# Z7_POWER1.net
KiCad netlist of a schematic drawn in Altium Designer
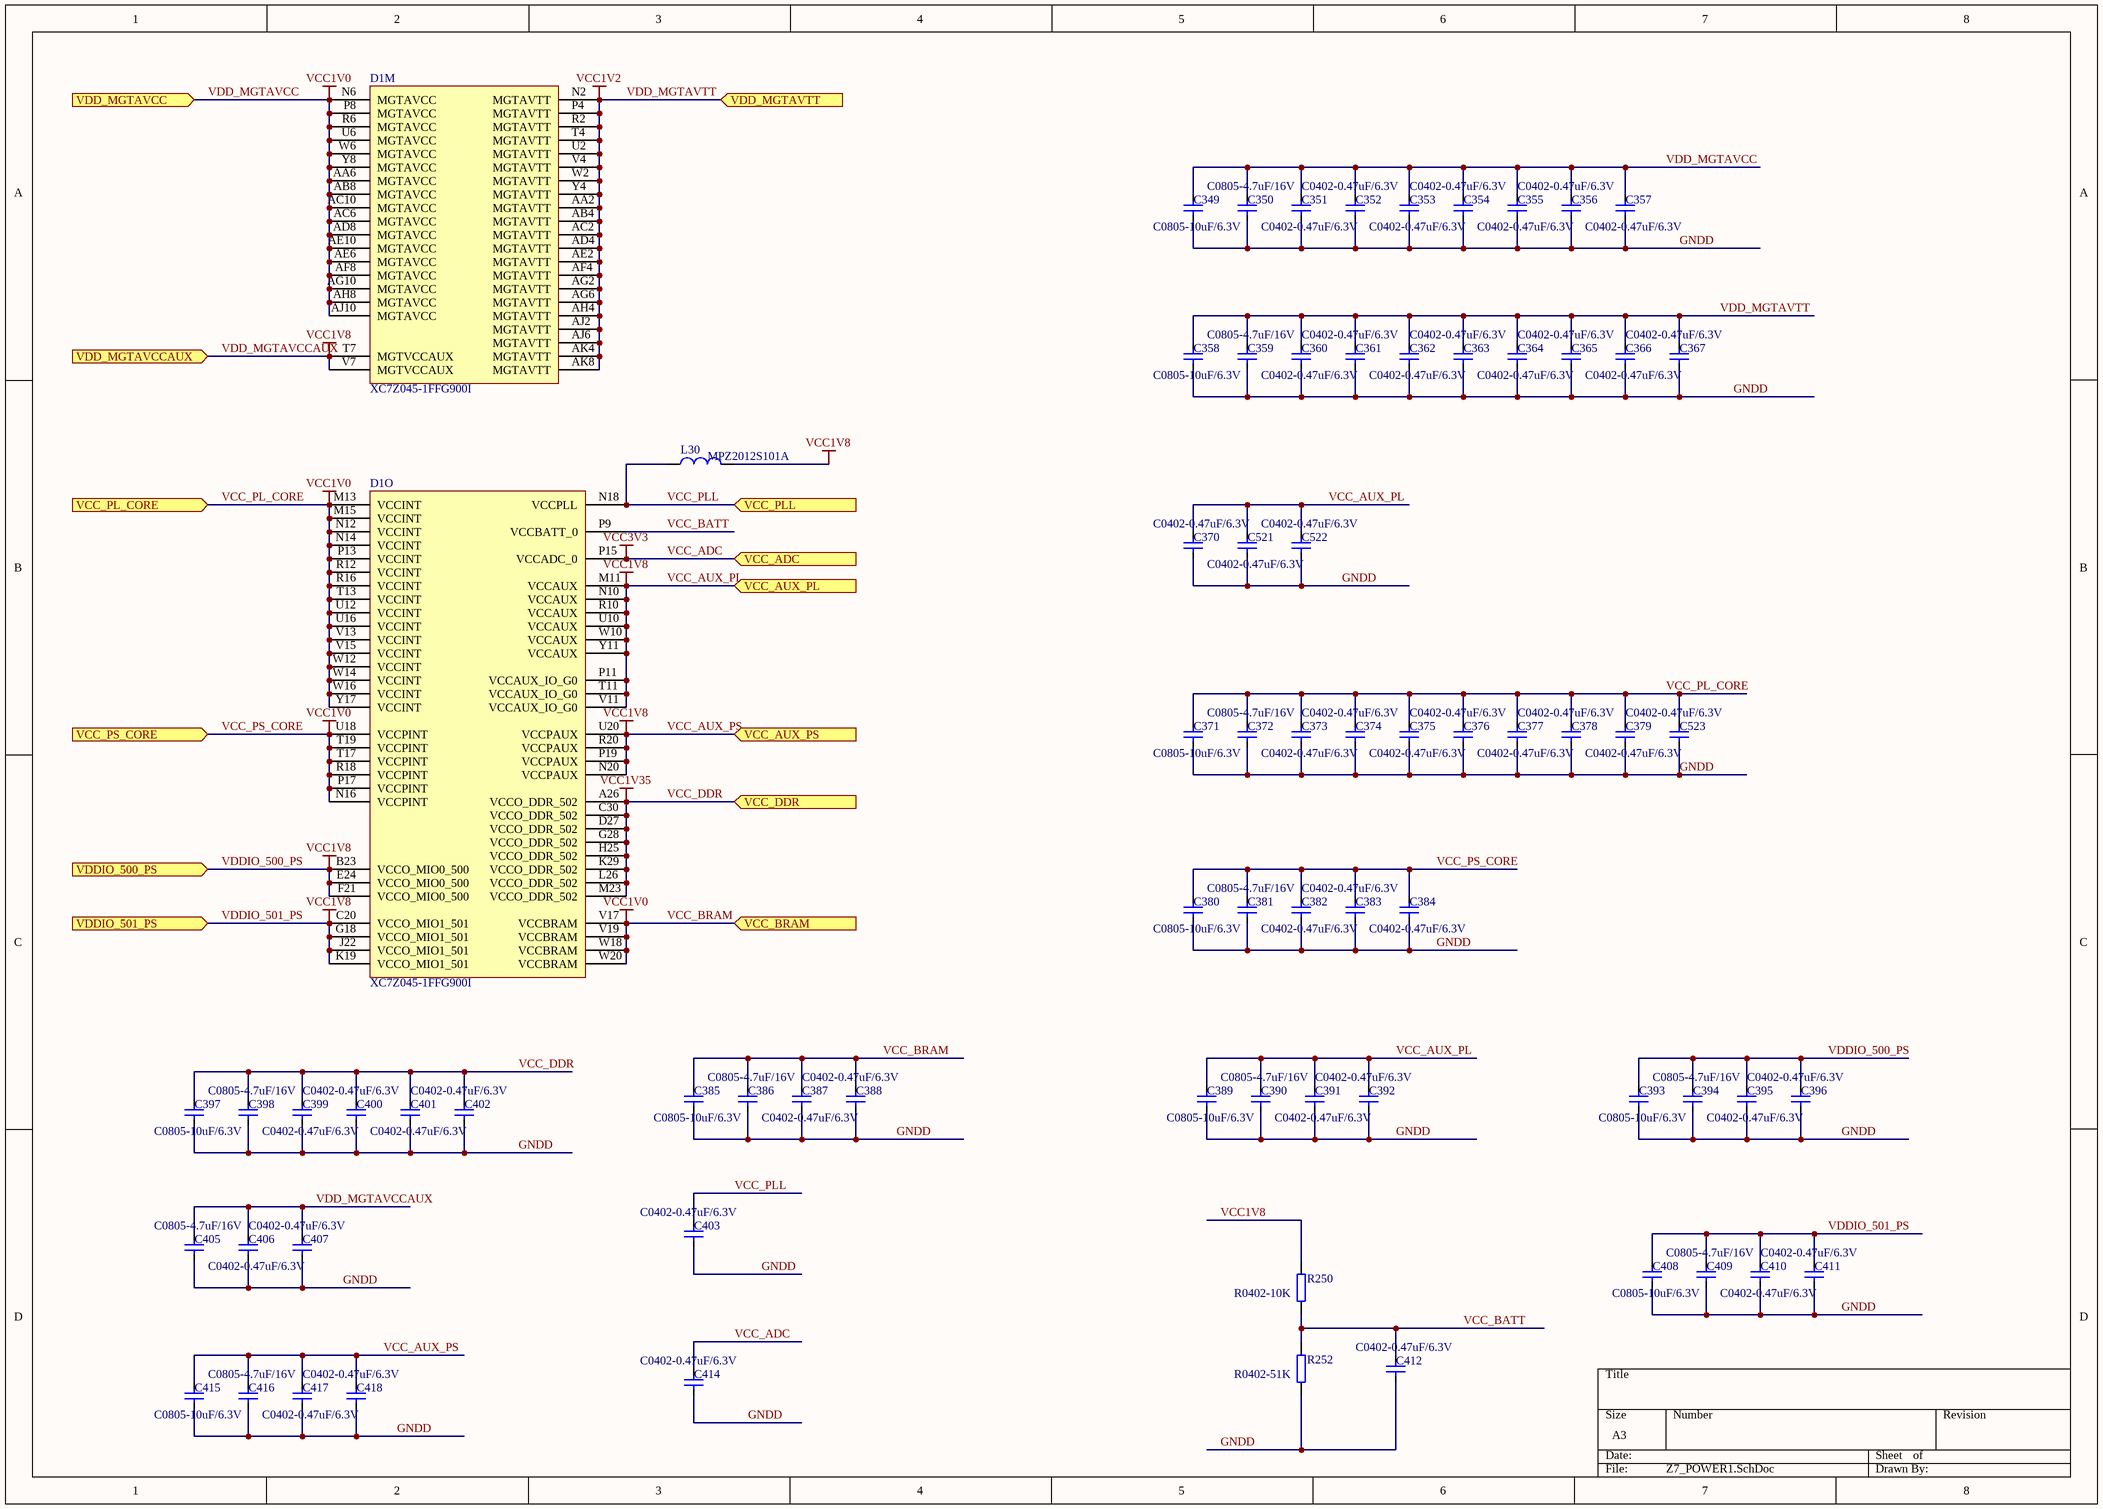
[diagram p0: Z7_POWER1.SchDoc]

(export (version "E")
  (design (tool "Eeschema 10.0.6"))
  (components
    (comp (ref "C349")
      (value "C0805-10uF/6.3V")
      (footprint "C0805")
      (fields (field (name "SCHEMATIC_PART") "CAP"))
      (libsource (lib "Database_Libs1") (part "CAP"))
    )
    (comp (ref "C350")
      (value "C0805-4.7uF/16V")
      (footprint "C0805")
      (description "X7R")
      (fields (field (name "SCHEMATIC_PART") "CAP") (field (name "MANUFACTURER") "SAMSUNG"))
      (libsource (lib "Database_Libs1") (part "CAP"))
    )
    (comp (ref "C351")
      (value "C0402-0.47uF/6.3V")
      (footprint "C0402")
      (description "X7R")
      (fields (field (name "SCHEMATIC_PART") "CAP") (field (name "MANUFACTURER") "SAMSUNG"))
      (libsource (lib "Database_Libs1") (part "CAP"))
    )
    (comp (ref "C352")
      (value "C0402-0.47uF/6.3V")
      (footprint "C0402")
      (description "X7R")
      (fields (field (name "SCHEMATIC_PART") "CAP") (field (name "MANUFACTURER") "SAMSUNG"))
      (libsource (lib "Database_Libs1") (part "CAP"))
    )
    (comp (ref "C353")
      (value "C0402-0.47uF/6.3V")
      (footprint "C0402")
      (description "X7R")
      (fields (field (name "SCHEMATIC_PART") "CAP") (field (name "MANUFACTURER") "SAMSUNG"))
      (libsource (lib "Database_Libs1") (part "CAP"))
    )
    (comp (ref "C354")
      (value "C0402-0.47uF/6.3V")
      (footprint "C0402")
      (description "X7R")
      (fields (field (name "SCHEMATIC_PART") "CAP") (field (name "MANUFACTURER") "SAMSUNG"))
      (libsource (lib "Database_Libs1") (part "CAP"))
    )
    (comp (ref "C355")
      (value "C0402-0.47uF/6.3V")
      (footprint "C0402")
      (description "X7R")
      (fields (field (name "SCHEMATIC_PART") "CAP") (field (name "MANUFACTURER") "SAMSUNG"))
      (libsource (lib "Database_Libs1") (part "CAP"))
    )
    (comp (ref "C356")
      (value "C0402-0.47uF/6.3V")
      (footprint "C0402")
      (description "X7R")
      (fields (field (name "SCHEMATIC_PART") "CAP") (field (name "MANUFACTURER") "SAMSUNG"))
      (libsource (lib "Database_Libs1") (part "CAP"))
    )
    (comp (ref "C357")
      (value "C0402-0.47uF/6.3V")
      (footprint "C0402")
      (description "X7R")
      (fields (field (name "SCHEMATIC_PART") "CAP") (field (name "MANUFACTURER") "SAMSUNG"))
      (libsource (lib "Database_Libs1") (part "CAP"))
    )
    (comp (ref "C358")
      (value "C0805-10uF/6.3V")
      (footprint "C0805")
      (fields (field (name "SCHEMATIC_PART") "CAP"))
      (libsource (lib "Database_Libs1") (part "CAP"))
    )
    (comp (ref "C359")
      (value "C0805-4.7uF/16V")
      (footprint "C0805")
      (description "X7R")
      (fields (field (name "SCHEMATIC_PART") "CAP") (field (name "MANUFACTURER") "SAMSUNG"))
      (libsource (lib "Database_Libs1") (part "CAP"))
    )
    (comp (ref "C360")
      (value "C0402-0.47uF/6.3V")
      (footprint "C0402")
      (description "X7R")
      (fields (field (name "SCHEMATIC_PART") "CAP") (field (name "MANUFACTURER") "SAMSUNG"))
      (libsource (lib "Database_Libs1") (part "CAP"))
    )
    (comp (ref "C361")
      (value "C0402-0.47uF/6.3V")
      (footprint "C0402")
      (description "X7R")
      (fields (field (name "SCHEMATIC_PART") "CAP") (field (name "MANUFACTURER") "SAMSUNG"))
      (libsource (lib "Database_Libs1") (part "CAP"))
    )
    (comp (ref "C362")
      (value "C0402-0.47uF/6.3V")
      (footprint "C0402")
      (description "X7R")
      (fields (field (name "SCHEMATIC_PART") "CAP") (field (name "MANUFACTURER") "SAMSUNG"))
      (libsource (lib "Database_Libs1") (part "CAP"))
    )
    (comp (ref "C363")
      (value "C0402-0.47uF/6.3V")
      (footprint "C0402")
      (description "X7R")
      (fields (field (name "SCHEMATIC_PART") "CAP") (field (name "MANUFACTURER") "SAMSUNG"))
      (libsource (lib "Database_Libs1") (part "CAP"))
    )
    (comp (ref "C364")
      (value "C0402-0.47uF/6.3V")
      (footprint "C0402")
      (description "X7R")
      (fields (field (name "SCHEMATIC_PART") "CAP") (field (name "MANUFACTURER") "SAMSUNG"))
      (libsource (lib "Database_Libs1") (part "CAP"))
    )
    (comp (ref "C365")
      (value "C0402-0.47uF/6.3V")
      (footprint "C0402")
      (description "X7R")
      (fields (field (name "SCHEMATIC_PART") "CAP") (field (name "MANUFACTURER") "SAMSUNG"))
      (libsource (lib "Database_Libs1") (part "CAP"))
    )
    (comp (ref "C366")
      (value "C0402-0.47uF/6.3V")
      (footprint "C0402")
      (description "X7R")
      (fields (field (name "SCHEMATIC_PART") "CAP") (field (name "MANUFACTURER") "SAMSUNG"))
      (libsource (lib "Database_Libs1") (part "CAP"))
    )
    (comp (ref "C367")
      (value "C0402-0.47uF/6.3V")
      (footprint "C0402")
      (description "X7R")
      (fields (field (name "SCHEMATIC_PART") "CAP") (field (name "MANUFACTURER") "SAMSUNG"))
      (libsource (lib "Database_Libs1") (part "CAP"))
    )
    (comp (ref "C370")
      (value "C0402-0.47uF/6.3V")
      (footprint "C0402")
      (description "X7R")
      (fields (field (name "SCHEMATIC_PART") "CAP") (field (name "MANUFACTURER") "SAMSUNG"))
      (libsource (lib "Database_Libs1") (part "CAP"))
    )
    (comp (ref "C371")
      (value "C0805-10uF/6.3V")
      (footprint "C0805")
      (fields (field (name "SCHEMATIC_PART") "CAP"))
      (libsource (lib "Database_Libs1") (part "CAP"))
    )
    (comp (ref "C372")
      (value "C0805-4.7uF/16V")
      (footprint "C0805")
      (description "X7R")
      (fields (field (name "SCHEMATIC_PART") "CAP") (field (name "MANUFACTURER") "SAMSUNG"))
      (libsource (lib "Database_Libs1") (part "CAP"))
    )
    (comp (ref "C373")
      (value "C0402-0.47uF/6.3V")
      (footprint "C0402")
      (description "X7R")
      (fields (field (name "SCHEMATIC_PART") "CAP") (field (name "MANUFACTURER") "SAMSUNG"))
      (libsource (lib "Database_Libs1") (part "CAP"))
    )
    (comp (ref "C374")
      (value "C0402-0.47uF/6.3V")
      (footprint "C0402")
      (description "X7R")
      (fields (field (name "SCHEMATIC_PART") "CAP") (field (name "MANUFACTURER") "SAMSUNG"))
      (libsource (lib "Database_Libs1") (part "CAP"))
    )
    (comp (ref "C375")
      (value "C0402-0.47uF/6.3V")
      (footprint "C0402")
      (description "X7R")
      (fields (field (name "SCHEMATIC_PART") "CAP") (field (name "MANUFACTURER") "SAMSUNG"))
      (libsource (lib "Database_Libs1") (part "CAP"))
    )
    (comp (ref "C376")
      (value "C0402-0.47uF/6.3V")
      (footprint "C0402")
      (description "X7R")
      (fields (field (name "SCHEMATIC_PART") "CAP") (field (name "MANUFACTURER") "SAMSUNG"))
      (libsource (lib "Database_Libs1") (part "CAP"))
    )
    (comp (ref "C377")
      (value "C0402-0.47uF/6.3V")
      (footprint "C0402")
      (description "X7R")
      (fields (field (name "SCHEMATIC_PART") "CAP") (field (name "MANUFACTURER") "SAMSUNG"))
      (libsource (lib "Database_Libs1") (part "CAP"))
    )
    (comp (ref "C378")
      (value "C0402-0.47uF/6.3V")
      (footprint "C0402")
      (description "X7R")
      (fields (field (name "SCHEMATIC_PART") "CAP") (field (name "MANUFACTURER") "SAMSUNG"))
      (libsource (lib "Database_Libs1") (part "CAP"))
    )
    (comp (ref "C379")
      (value "C0402-0.47uF/6.3V")
      (footprint "C0402")
      (description "X7R")
      (fields (field (name "SCHEMATIC_PART") "CAP") (field (name "MANUFACTURER") "SAMSUNG"))
      (libsource (lib "Database_Libs1") (part "CAP"))
    )
    (comp (ref "C380")
      (value "C0805-10uF/6.3V")
      (footprint "C0805")
      (fields (field (name "SCHEMATIC_PART") "CAP"))
      (libsource (lib "Database_Libs1") (part "CAP"))
    )
    (comp (ref "C381")
      (value "C0805-4.7uF/16V")
      (footprint "C0805")
      (description "X7R")
      (fields (field (name "SCHEMATIC_PART") "CAP") (field (name "MANUFACTURER") "SAMSUNG"))
      (libsource (lib "Database_Libs1") (part "CAP"))
    )
    (comp (ref "C382")
      (value "C0402-0.47uF/6.3V")
      (footprint "C0402")
      (description "X7R")
      (fields (field (name "SCHEMATIC_PART") "CAP") (field (name "MANUFACTURER") "SAMSUNG"))
      (libsource (lib "Database_Libs1") (part "CAP"))
    )
    (comp (ref "C383")
      (value "C0402-0.47uF/6.3V")
      (footprint "C0402")
      (description "X7R")
      (fields (field (name "SCHEMATIC_PART") "CAP") (field (name "MANUFACTURER") "SAMSUNG"))
      (libsource (lib "Database_Libs1") (part "CAP"))
    )
    (comp (ref "C384")
      (value "C0402-0.47uF/6.3V")
      (footprint "C0402")
      (description "X7R")
      (fields (field (name "SCHEMATIC_PART") "CAP") (field (name "MANUFACTURER") "SAMSUNG"))
      (libsource (lib "Database_Libs1") (part "CAP"))
    )
    (comp (ref "C385")
      (value "C0805-10uF/6.3V")
      (footprint "C0805")
      (fields (field (name "SCHEMATIC_PART") "CAP"))
      (libsource (lib "Database_Libs1") (part "CAP"))
    )
    (comp (ref "C386")
      (value "C0805-4.7uF/16V")
      (footprint "C0805")
      (description "X7R")
      (fields (field (name "SCHEMATIC_PART") "CAP") (field (name "MANUFACTURER") "SAMSUNG"))
      (libsource (lib "Database_Libs1") (part "CAP"))
    )
    (comp (ref "C387")
      (value "C0402-0.47uF/6.3V")
      (footprint "C0402")
      (description "X7R")
      (fields (field (name "SCHEMATIC_PART") "CAP") (field (name "MANUFACTURER") "SAMSUNG"))
      (libsource (lib "Database_Libs1") (part "CAP"))
    )
    (comp (ref "C388")
      (value "C0402-0.47uF/6.3V")
      (footprint "C0402")
      (description "X7R")
      (fields (field (name "SCHEMATIC_PART") "CAP") (field (name "MANUFACTURER") "SAMSUNG"))
      (libsource (lib "Database_Libs1") (part "CAP"))
    )
    (comp (ref "C389")
      (value "C0805-10uF/6.3V")
      (footprint "C0805")
      (fields (field (name "SCHEMATIC_PART") "CAP"))
      (libsource (lib "Database_Libs1") (part "CAP"))
    )
    (comp (ref "C390")
      (value "C0805-4.7uF/16V")
      (footprint "C0805")
      (description "X7R")
      (fields (field (name "SCHEMATIC_PART") "CAP") (field (name "MANUFACTURER") "SAMSUNG"))
      (libsource (lib "Database_Libs1") (part "CAP"))
    )
    (comp (ref "C391")
      (value "C0402-0.47uF/6.3V")
      (footprint "C0402")
      (description "X7R")
      (fields (field (name "SCHEMATIC_PART") "CAP") (field (name "MANUFACTURER") "SAMSUNG"))
      (libsource (lib "Database_Libs1") (part "CAP"))
    )
    (comp (ref "C392")
      (value "C0402-0.47uF/6.3V")
      (footprint "C0402")
      (description "X7R")
      (fields (field (name "SCHEMATIC_PART") "CAP") (field (name "MANUFACTURER") "SAMSUNG"))
      (libsource (lib "Database_Libs1") (part "CAP"))
    )
    (comp (ref "C393")
      (value "C0805-10uF/6.3V")
      (footprint "C0805")
      (fields (field (name "SCHEMATIC_PART") "CAP"))
      (libsource (lib "Database_Libs1") (part "CAP"))
    )
    (comp (ref "C394")
      (value "C0805-4.7uF/16V")
      (footprint "C0805")
      (description "X7R")
      (fields (field (name "SCHEMATIC_PART") "CAP") (field (name "MANUFACTURER") "SAMSUNG"))
      (libsource (lib "Database_Libs1") (part "CAP"))
    )
    (comp (ref "C395")
      (value "C0402-0.47uF/6.3V")
      (footprint "C0402")
      (description "X7R")
      (fields (field (name "SCHEMATIC_PART") "CAP") (field (name "MANUFACTURER") "SAMSUNG"))
      (libsource (lib "Database_Libs1") (part "CAP"))
    )
    (comp (ref "C396")
      (value "C0402-0.47uF/6.3V")
      (footprint "C0402")
      (description "X7R")
      (fields (field (name "SCHEMATIC_PART") "CAP") (field (name "MANUFACTURER") "SAMSUNG"))
      (libsource (lib "Database_Libs1") (part "CAP"))
    )
    (comp (ref "C397")
      (value "C0805-10uF/6.3V")
      (footprint "C0805")
      (fields (field (name "SCHEMATIC_PART") "CAP"))
      (libsource (lib "Database_Libs1") (part "CAP"))
    )
    (comp (ref "C398")
      (value "C0805-4.7uF/16V")
      (footprint "C0805")
      (description "X7R")
      (fields (field (name "SCHEMATIC_PART") "CAP") (field (name "MANUFACTURER") "SAMSUNG"))
      (libsource (lib "Database_Libs1") (part "CAP"))
    )
    (comp (ref "C399")
      (value "C0402-0.47uF/6.3V")
      (footprint "C0402")
      (description "X7R")
      (fields (field (name "SCHEMATIC_PART") "CAP") (field (name "MANUFACTURER") "SAMSUNG"))
      (libsource (lib "Database_Libs1") (part "CAP"))
    )
    (comp (ref "C400")
      (value "C0402-0.47uF/6.3V")
      (footprint "C0402")
      (description "X7R")
      (fields (field (name "SCHEMATIC_PART") "CAP") (field (name "MANUFACTURER") "SAMSUNG"))
      (libsource (lib "Database_Libs1") (part "CAP"))
    )
    (comp (ref "C401")
      (value "C0402-0.47uF/6.3V")
      (footprint "C0402")
      (description "X7R")
      (fields (field (name "SCHEMATIC_PART") "CAP") (field (name "MANUFACTURER") "SAMSUNG"))
      (libsource (lib "Database_Libs1") (part "CAP"))
    )
    (comp (ref "C402")
      (value "C0402-0.47uF/6.3V")
      (footprint "C0402")
      (description "X7R")
      (fields (field (name "SCHEMATIC_PART") "CAP") (field (name "MANUFACTURER") "SAMSUNG"))
      (libsource (lib "Database_Libs1") (part "CAP"))
    )
    (comp (ref "C403")
      (value "C0402-0.47uF/6.3V")
      (footprint "C0402")
      (description "X7R")
      (fields (field (name "SCHEMATIC_PART") "CAP") (field (name "MANUFACTURER") "SAMSUNG"))
      (libsource (lib "Database_Libs1") (part "CAP"))
    )
    (comp (ref "C405")
      (value "C0805-4.7uF/16V")
      (footprint "C0805")
      (description "X7R")
      (fields (field (name "SCHEMATIC_PART") "CAP") (field (name "MANUFACTURER") "SAMSUNG"))
      (libsource (lib "Database_Libs1") (part "CAP"))
    )
    (comp (ref "C406")
      (value "C0402-0.47uF/6.3V")
      (footprint "C0402")
      (description "X7R")
      (fields (field (name "SCHEMATIC_PART") "CAP") (field (name "MANUFACTURER") "SAMSUNG"))
      (libsource (lib "Database_Libs1") (part "CAP"))
    )
    (comp (ref "C407")
      (value "C0402-0.47uF/6.3V")
      (footprint "C0402")
      (description "X7R")
      (fields (field (name "SCHEMATIC_PART") "CAP") (field (name "MANUFACTURER") "SAMSUNG"))
      (libsource (lib "Database_Libs1") (part "CAP"))
    )
    (comp (ref "C408")
      (value "C0805-10uF/6.3V")
      (footprint "C0805")
      (fields (field (name "SCHEMATIC_PART") "CAP"))
      (libsource (lib "Database_Libs1") (part "CAP"))
    )
    (comp (ref "C409")
      (value "C0805-4.7uF/16V")
      (footprint "C0805")
      (description "X7R")
      (fields (field (name "SCHEMATIC_PART") "CAP") (field (name "MANUFACTURER") "SAMSUNG"))
      (libsource (lib "Database_Libs1") (part "CAP"))
    )
    (comp (ref "C410")
      (value "C0402-0.47uF/6.3V")
      (footprint "C0402")
      (description "X7R")
      (fields (field (name "SCHEMATIC_PART") "CAP") (field (name "MANUFACTURER") "SAMSUNG"))
      (libsource (lib "Database_Libs1") (part "CAP"))
    )
    (comp (ref "C411")
      (value "C0402-0.47uF/6.3V")
      (footprint "C0402")
      (description "X7R")
      (fields (field (name "SCHEMATIC_PART") "CAP") (field (name "MANUFACTURER") "SAMSUNG"))
      (libsource (lib "Database_Libs1") (part "CAP"))
    )
    (comp (ref "C412")
      (value "C0402-0.47uF/6.3V")
      (footprint "C0402")
      (description "X7R")
      (fields (field (name "SCHEMATIC_PART") "CAP") (field (name "MANUFACTURER") "SAMSUNG"))
      (libsource (lib "Database_Libs1") (part "CAP"))
    )
    (comp (ref "C414")
      (value "C0402-0.47uF/6.3V")
      (footprint "C0402")
      (description "X7R")
      (fields (field (name "SCHEMATIC_PART") "CAP") (field (name "MANUFACTURER") "SAMSUNG"))
      (libsource (lib "Database_Libs1") (part "CAP"))
    )
    (comp (ref "C415")
      (value "C0805-10uF/6.3V")
      (footprint "C0805")
      (fields (field (name "SCHEMATIC_PART") "CAP"))
      (libsource (lib "Database_Libs1") (part "CAP"))
    )
    (comp (ref "C416")
      (value "C0805-4.7uF/16V")
      (footprint "C0805")
      (description "X7R")
      (fields (field (name "SCHEMATIC_PART") "CAP") (field (name "MANUFACTURER") "SAMSUNG"))
      (libsource (lib "Database_Libs1") (part "CAP"))
    )
    (comp (ref "C417")
      (value "C0402-0.47uF/6.3V")
      (footprint "C0402")
      (description "X7R")
      (fields (field (name "SCHEMATIC_PART") "CAP") (field (name "MANUFACTURER") "SAMSUNG"))
      (libsource (lib "Database_Libs1") (part "CAP"))
    )
    (comp (ref "C418")
      (value "C0402-0.47uF/6.3V")
      (footprint "C0402")
      (description "X7R")
      (fields (field (name "SCHEMATIC_PART") "CAP") (field (name "MANUFACTURER") "SAMSUNG"))
      (libsource (lib "Database_Libs1") (part "CAP"))
    )
    (comp (ref "C521")
      (value "C0402-0.47uF/6.3V")
      (footprint "C0402")
      (description "X7R")
      (fields (field (name "SCHEMATIC_PART") "CAP") (field (name "MANUFACTURER") "SAMSUNG"))
      (libsource (lib "Database_Libs1") (part "CAP"))
    )
    (comp (ref "C522")
      (value "C0402-0.47uF/6.3V")
      (footprint "C0402")
      (description "X7R")
      (fields (field (name "SCHEMATIC_PART") "CAP") (field (name "MANUFACTURER") "SAMSUNG"))
      (libsource (lib "Database_Libs1") (part "CAP"))
    )
    (comp (ref "C523")
      (value "C0402-0.47uF/6.3V")
      (footprint "C0402")
      (description "X7R")
      (fields (field (name "SCHEMATIC_PART") "CAP") (field (name "MANUFACTURER") "SAMSUNG"))
      (libsource (lib "Database_Libs1") (part "CAP"))
    )
    (comp (ref "D1")
      (value "XC7Z045-1FFG900I")
      (footprint "FFG900")
      (fields (field (name "GENERIC PART NUMBER") "XC7Z045") (field (name "MANUFACTURER") "Xilinx"))
      (libsource (lib "Xilinx Zynq-7000") (part "XC7Z045-1FFG900I"))
    )
    (comp (ref "L30")
      (value "MPZ2012S101A")
      (footprint "R0805")
      (fields (field (name "SCHEMATIC_PART") "BEAD") (field (name "MANUFACTURER") "TDK"))
      (libsource (lib "Database_Libs1") (part "BEAD"))
    )
    (comp (ref "R250")
      (value "R0402-10K")
      (footprint "R0402")
      (fields (field (name "SCHEMATIC_PART") "RES") (field (name "MANUFACTURER") "SAMSUNG"))
      (libsource (lib "Database_Libs1") (part "RES"))
    )
    (comp (ref "R252")
      (value "R0402-51K")
      (footprint "R0402")
      (fields (field (name "SCHEMATIC_PART") "RES") (field (name "MANUFACTURER") "SAMSUNG"))
      (libsource (lib "Database_Libs1") (part "RES"))
    )
  )
  (nets
    (net (code "1") (name "/GNDD") (class "Default")
      (node (ref "C349") (pin "2") (pinfunction "2_2") (pintype "passive"))
      (node (ref "C350") (pin "2") (pinfunction "2_2") (pintype "passive"))
      (node (ref "C351") (pin "2") (pinfunction "2_2") (pintype "passive"))
      (node (ref "C352") (pin "2") (pinfunction "2_2") (pintype "passive"))
      (node (ref "C353") (pin "2") (pinfunction "2_2") (pintype "passive"))
      (node (ref "C354") (pin "2") (pinfunction "2_2") (pintype "passive"))
      (node (ref "C355") (pin "2") (pinfunction "2_2") (pintype "passive"))
      (node (ref "C356") (pin "2") (pinfunction "2_2") (pintype "passive"))
      (node (ref "C357") (pin "2") (pinfunction "2_2") (pintype "passive"))
      (node (ref "C358") (pin "2") (pinfunction "2_2") (pintype "passive"))
      (node (ref "C359") (pin "2") (pinfunction "2_2") (pintype "passive"))
      (node (ref "C360") (pin "2") (pinfunction "2_2") (pintype "passive"))
      (node (ref "C361") (pin "2") (pinfunction "2_2") (pintype "passive"))
      (node (ref "C362") (pin "2") (pinfunction "2_2") (pintype "passive"))
      (node (ref "C363") (pin "2") (pinfunction "2_2") (pintype "passive"))
      (node (ref "C364") (pin "2") (pinfunction "2_2") (pintype "passive"))
      (node (ref "C365") (pin "2") (pinfunction "2_2") (pintype "passive"))
      (node (ref "C366") (pin "2") (pinfunction "2_2") (pintype "passive"))
      (node (ref "C367") (pin "2") (pinfunction "2_2") (pintype "passive"))
      (node (ref "C370") (pin "2") (pinfunction "2_2") (pintype "passive"))
      (node (ref "C371") (pin "2") (pinfunction "2_2") (pintype "passive"))
      (node (ref "C372") (pin "2") (pinfunction "2_2") (pintype "passive"))
      (node (ref "C373") (pin "2") (pinfunction "2_2") (pintype "passive"))
      (node (ref "C374") (pin "2") (pinfunction "2_2") (pintype "passive"))
      (node (ref "C375") (pin "2") (pinfunction "2_2") (pintype "passive"))
      (node (ref "C376") (pin "2") (pinfunction "2_2") (pintype "passive"))
      (node (ref "C377") (pin "2") (pinfunction "2_2") (pintype "passive"))
      (node (ref "C378") (pin "2") (pinfunction "2_2") (pintype "passive"))
      (node (ref "C379") (pin "2") (pinfunction "2_2") (pintype "passive"))
      (node (ref "C380") (pin "2") (pinfunction "2_2") (pintype "passive"))
      (node (ref "C381") (pin "2") (pinfunction "2_2") (pintype "passive"))
      (node (ref "C382") (pin "2") (pinfunction "2_2") (pintype "passive"))
      (node (ref "C383") (pin "2") (pinfunction "2_2") (pintype "passive"))
      (node (ref "C384") (pin "2") (pinfunction "2_2") (pintype "passive"))
      (node (ref "C385") (pin "2") (pinfunction "2_2") (pintype "passive"))
      (node (ref "C386") (pin "2") (pinfunction "2_2") (pintype "passive"))
      (node (ref "C387") (pin "2") (pinfunction "2_2") (pintype "passive"))
      (node (ref "C388") (pin "2") (pinfunction "2_2") (pintype "passive"))
      (node (ref "C389") (pin "2") (pinfunction "2_2") (pintype "passive"))
      (node (ref "C390") (pin "2") (pinfunction "2_2") (pintype "passive"))
      (node (ref "C391") (pin "2") (pinfunction "2_2") (pintype "passive"))
      (node (ref "C392") (pin "2") (pinfunction "2_2") (pintype "passive"))
      (node (ref "C393") (pin "2") (pinfunction "2_2") (pintype "passive"))
      (node (ref "C394") (pin "2") (pinfunction "2_2") (pintype "passive"))
      (node (ref "C395") (pin "2") (pinfunction "2_2") (pintype "passive"))
      (node (ref "C396") (pin "2") (pinfunction "2_2") (pintype "passive"))
      (node (ref "C397") (pin "2") (pinfunction "2_2") (pintype "passive"))
      (node (ref "C398") (pin "2") (pinfunction "2_2") (pintype "passive"))
      (node (ref "C399") (pin "2") (pinfunction "2_2") (pintype "passive"))
      (node (ref "C400") (pin "2") (pinfunction "2_2") (pintype "passive"))
      (node (ref "C401") (pin "2") (pinfunction "2_2") (pintype "passive"))
      (node (ref "C402") (pin "2") (pinfunction "2_2") (pintype "passive"))
      (node (ref "C403") (pin "2") (pinfunction "2_2") (pintype "passive"))
      (node (ref "C405") (pin "2") (pinfunction "2_2") (pintype "passive"))
      (node (ref "C406") (pin "2") (pinfunction "2_2") (pintype "passive"))
      (node (ref "C407") (pin "2") (pinfunction "2_2") (pintype "passive"))
      (node (ref "C408") (pin "2") (pinfunction "2_2") (pintype "passive"))
      (node (ref "C409") (pin "2") (pinfunction "2_2") (pintype "passive"))
      (node (ref "C410") (pin "2") (pinfunction "2_2") (pintype "passive"))
      (node (ref "C411") (pin "2") (pinfunction "2_2") (pintype "passive"))
      (node (ref "C412") (pin "2") (pinfunction "2_2") (pintype "passive"))
      (node (ref "C414") (pin "2") (pinfunction "2_2") (pintype "passive"))
      (node (ref "C415") (pin "2") (pinfunction "2_2") (pintype "passive"))
      (node (ref "C416") (pin "2") (pinfunction "2_2") (pintype "passive"))
      (node (ref "C417") (pin "2") (pinfunction "2_2") (pintype "passive"))
      (node (ref "C418") (pin "2") (pinfunction "2_2") (pintype "passive"))
      (node (ref "C521") (pin "2") (pinfunction "2_2") (pintype "passive"))
      (node (ref "C522") (pin "2") (pinfunction "2_2") (pintype "passive"))
      (node (ref "C523") (pin "2") (pinfunction "2_2") (pintype "passive"))
      (node (ref "R252") (pin "1") (pintype "passive"))
    )
    (net (code "2") (name "/VCC_BATT") (class "Default")
      (node (ref "C412") (pin "1") (pinfunction "1_1") (pintype "passive"))
      (node (ref "D1") (pin "P9") (pinfunction "VCCBATT_0_P9") (pintype "power_in"))
      (node (ref "R250") (pin "1") (pintype "passive"))
      (node (ref "R252") (pin "2") (pintype "passive"))
    )
    (net (code "3") (name "/VCC_PLL") (class "Default")
      (node (ref "C403") (pin "1") (pinfunction "1_1") (pintype "passive"))
      (node (ref "D1") (pin "N18") (pinfunction "VCCPLL_N18") (pintype "power_in"))
      (node (ref "L30") (pin "1") (pinfunction "1_1") (pintype "passive"))
    )
    (net (code "4") (name "VCC1V0") (class "Default")
      (node (ref "C349") (pin "1") (pinfunction "1_1") (pintype "passive"))
      (node (ref "C350") (pin "1") (pinfunction "1_1") (pintype "passive"))
      (node (ref "C351") (pin "1") (pinfunction "1_1") (pintype "passive"))
      (node (ref "C352") (pin "1") (pinfunction "1_1") (pintype "passive"))
      (node (ref "C353") (pin "1") (pinfunction "1_1") (pintype "passive"))
      (node (ref "C354") (pin "1") (pinfunction "1_1") (pintype "passive"))
      (node (ref "C355") (pin "1") (pinfunction "1_1") (pintype "passive"))
      (node (ref "C356") (pin "1") (pinfunction "1_1") (pintype "passive"))
      (node (ref "C357") (pin "1") (pinfunction "1_1") (pintype "passive"))
      (node (ref "C371") (pin "1") (pinfunction "1_1") (pintype "passive"))
      (node (ref "C372") (pin "1") (pinfunction "1_1") (pintype "passive"))
      (node (ref "C373") (pin "1") (pinfunction "1_1") (pintype "passive"))
      (node (ref "C374") (pin "1") (pinfunction "1_1") (pintype "passive"))
      (node (ref "C375") (pin "1") (pinfunction "1_1") (pintype "passive"))
      (node (ref "C376") (pin "1") (pinfunction "1_1") (pintype "passive"))
      (node (ref "C377") (pin "1") (pinfunction "1_1") (pintype "passive"))
      (node (ref "C378") (pin "1") (pinfunction "1_1") (pintype "passive"))
      (node (ref "C379") (pin "1") (pinfunction "1_1") (pintype "passive"))
      (node (ref "C380") (pin "1") (pinfunction "1_1") (pintype "passive"))
      (node (ref "C381") (pin "1") (pinfunction "1_1") (pintype "passive"))
      (node (ref "C382") (pin "1") (pinfunction "1_1") (pintype "passive"))
      (node (ref "C383") (pin "1") (pinfunction "1_1") (pintype "passive"))
      (node (ref "C384") (pin "1") (pinfunction "1_1") (pintype "passive"))
      (node (ref "C385") (pin "1") (pinfunction "1_1") (pintype "passive"))
      (node (ref "C386") (pin "1") (pinfunction "1_1") (pintype "passive"))
      (node (ref "C387") (pin "1") (pinfunction "1_1") (pintype "passive"))
      (node (ref "C388") (pin "1") (pinfunction "1_1") (pintype "passive"))
      (node (ref "C523") (pin "1") (pinfunction "1_1") (pintype "passive"))
      (node (ref "D1") (pin "AA6") (pinfunction "MGTAVCC_AA6") (pintype "power_in"))
      (node (ref "D1") (pin "AB8") (pinfunction "MGTAVCC_AB8") (pintype "power_in"))
      (node (ref "D1") (pin "AC10") (pinfunction "MGTAVCC_AC10") (pintype "power_in"))
      (node (ref "D1") (pin "AC6") (pinfunction "MGTAVCC_AC6") (pintype "power_in"))
      (node (ref "D1") (pin "AD8") (pinfunction "MGTAVCC_AD8") (pintype "power_in"))
      (node (ref "D1") (pin "AE10") (pinfunction "MGTAVCC_AE10") (pintype "power_in"))
      (node (ref "D1") (pin "AE6") (pinfunction "MGTAVCC_AE6") (pintype "power_in"))
      (node (ref "D1") (pin "AF8") (pinfunction "MGTAVCC_AF8") (pintype "power_in"))
      (node (ref "D1") (pin "AG10") (pinfunction "MGTAVCC_AG10") (pintype "power_in"))
      (node (ref "D1") (pin "AH8") (pinfunction "MGTAVCC_AH8") (pintype "power_in"))
      (node (ref "D1") (pin "AJ10") (pinfunction "MGTAVCC_AJ10") (pintype "power_in"))
      (node (ref "D1") (pin "M13") (pinfunction "VCCINT_M13") (pintype "power_in"))
      (node (ref "D1") (pin "M15") (pinfunction "VCCINT_M15") (pintype "power_in"))
      (node (ref "D1") (pin "N12") (pinfunction "VCCINT_N12") (pintype "power_in"))
      (node (ref "D1") (pin "N14") (pinfunction "VCCINT_N14") (pintype "power_in"))
      (node (ref "D1") (pin "N16") (pinfunction "VCCPINT_N16") (pintype "power_in"))
      (node (ref "D1") (pin "N6") (pinfunction "MGTAVCC_N6") (pintype "power_in"))
      (node (ref "D1") (pin "P13") (pinfunction "VCCINT_P13") (pintype "power_in"))
      (node (ref "D1") (pin "P17") (pinfunction "VCCPINT_P17") (pintype "power_in"))
      (node (ref "D1") (pin "P8") (pinfunction "MGTAVCC_P8") (pintype "power_in"))
      (node (ref "D1") (pin "R12") (pinfunction "VCCINT_R12") (pintype "power_in"))
      (node (ref "D1") (pin "R16") (pinfunction "VCCINT_R16") (pintype "power_in"))
      (node (ref "D1") (pin "R18") (pinfunction "VCCPINT_R18") (pintype "power_in"))
      (node (ref "D1") (pin "R6") (pinfunction "MGTAVCC_R6") (pintype "power_in"))
      (node (ref "D1") (pin "T13") (pinfunction "VCCINT_T13") (pintype "power_in"))
      (node (ref "D1") (pin "T17") (pinfunction "VCCPINT_T17") (pintype "power_in"))
      (node (ref "D1") (pin "T19") (pinfunction "VCCPINT_T19") (pintype "power_in"))
      (node (ref "D1") (pin "U12") (pinfunction "VCCINT_U12") (pintype "power_in"))
      (node (ref "D1") (pin "U16") (pinfunction "VCCINT_U16") (pintype "power_in"))
      (node (ref "D1") (pin "U18") (pinfunction "VCCPINT_U18") (pintype "power_in"))
      (node (ref "D1") (pin "U6") (pinfunction "MGTAVCC_U6") (pintype "power_in"))
      (node (ref "D1") (pin "V13") (pinfunction "VCCINT_V13") (pintype "power_in"))
      (node (ref "D1") (pin "V15") (pinfunction "VCCINT_V15") (pintype "power_in"))
      (node (ref "D1") (pin "V17") (pinfunction "VCCBRAM_V17") (pintype "power_in"))
      (node (ref "D1") (pin "V19") (pinfunction "VCCBRAM_V19") (pintype "power_in"))
      (node (ref "D1") (pin "W12") (pinfunction "VCCINT_W12") (pintype "power_in"))
      (node (ref "D1") (pin "W14") (pinfunction "VCCINT_W14") (pintype "power_in"))
      (node (ref "D1") (pin "W16") (pinfunction "VCCINT_W16") (pintype "power_in"))
      (node (ref "D1") (pin "W18") (pinfunction "VCCBRAM_W18") (pintype "power_in"))
      (node (ref "D1") (pin "W20") (pinfunction "VCCBRAM_W20") (pintype "power_in"))
      (node (ref "D1") (pin "W6") (pinfunction "MGTAVCC_W6") (pintype "power_in"))
      (node (ref "D1") (pin "Y17") (pinfunction "VCCINT_Y17") (pintype "power_in"))
      (node (ref "D1") (pin "Y8") (pinfunction "MGTAVCC_Y8") (pintype "power_in"))
    )
    (net (code "5") (name "VCC1V2") (class "Default")
      (node (ref "C358") (pin "1") (pinfunction "1_1") (pintype "passive"))
      (node (ref "C359") (pin "1") (pinfunction "1_1") (pintype "passive"))
      (node (ref "C360") (pin "1") (pinfunction "1_1") (pintype "passive"))
      (node (ref "C361") (pin "1") (pinfunction "1_1") (pintype "passive"))
      (node (ref "C362") (pin "1") (pinfunction "1_1") (pintype "passive"))
      (node (ref "C363") (pin "1") (pinfunction "1_1") (pintype "passive"))
      (node (ref "C364") (pin "1") (pinfunction "1_1") (pintype "passive"))
      (node (ref "C365") (pin "1") (pinfunction "1_1") (pintype "passive"))
      (node (ref "C366") (pin "1") (pinfunction "1_1") (pintype "passive"))
      (node (ref "C367") (pin "1") (pinfunction "1_1") (pintype "passive"))
      (node (ref "D1") (pin "AA2") (pinfunction "MGTAVTT_AA2") (pintype "power_in"))
      (node (ref "D1") (pin "AB4") (pinfunction "MGTAVTT_AB4") (pintype "power_in"))
      (node (ref "D1") (pin "AC2") (pinfunction "MGTAVTT_AC2") (pintype "power_in"))
      (node (ref "D1") (pin "AD4") (pinfunction "MGTAVTT_AD4") (pintype "power_in"))
      (node (ref "D1") (pin "AE2") (pinfunction "MGTAVTT_AE2") (pintype "power_in"))
      (node (ref "D1") (pin "AF4") (pinfunction "MGTAVTT_AF4") (pintype "power_in"))
      (node (ref "D1") (pin "AG2") (pinfunction "MGTAVTT_AG2") (pintype "power_in"))
      (node (ref "D1") (pin "AG6") (pinfunction "MGTAVTT_AG6") (pintype "power_in"))
      (node (ref "D1") (pin "AH4") (pinfunction "MGTAVTT_AH4") (pintype "power_in"))
      (node (ref "D1") (pin "AJ2") (pinfunction "MGTAVTT_AJ2") (pintype "power_in"))
      (node (ref "D1") (pin "AJ6") (pinfunction "MGTAVTT_AJ6") (pintype "power_in"))
      (node (ref "D1") (pin "AK4") (pinfunction "MGTAVTT_AK4") (pintype "power_in"))
      (node (ref "D1") (pin "AK8") (pinfunction "MGTAVTT_AK8") (pintype "power_in"))
      (node (ref "D1") (pin "N2") (pinfunction "MGTAVTT_N2") (pintype "power_in"))
      (node (ref "D1") (pin "P4") (pinfunction "MGTAVTT_P4") (pintype "power_in"))
      (node (ref "D1") (pin "R2") (pinfunction "MGTAVTT_R2") (pintype "power_in"))
      (node (ref "D1") (pin "T4") (pinfunction "MGTAVTT_T4") (pintype "power_in"))
      (node (ref "D1") (pin "U2") (pinfunction "MGTAVTT_U2") (pintype "power_in"))
      (node (ref "D1") (pin "V4") (pinfunction "MGTAVTT_V4") (pintype "power_in"))
      (node (ref "D1") (pin "W2") (pinfunction "MGTAVTT_W2") (pintype "power_in"))
      (node (ref "D1") (pin "Y4") (pinfunction "MGTAVTT_Y4") (pintype "power_in"))
    )
    (net (code "6") (name "VCC1V8") (class "Default")
      (node (ref "C370") (pin "1") (pinfunction "1_1") (pintype "passive"))
      (node (ref "C389") (pin "1") (pinfunction "1_1") (pintype "passive"))
      (node (ref "C390") (pin "1") (pinfunction "1_1") (pintype "passive"))
      (node (ref "C391") (pin "1") (pinfunction "1_1") (pintype "passive"))
      (node (ref "C392") (pin "1") (pinfunction "1_1") (pintype "passive"))
      (node (ref "C393") (pin "1") (pinfunction "1_1") (pintype "passive"))
      (node (ref "C394") (pin "1") (pinfunction "1_1") (pintype "passive"))
      (node (ref "C395") (pin "1") (pinfunction "1_1") (pintype "passive"))
      (node (ref "C396") (pin "1") (pinfunction "1_1") (pintype "passive"))
      (node (ref "C405") (pin "1") (pinfunction "1_1") (pintype "passive"))
      (node (ref "C406") (pin "1") (pinfunction "1_1") (pintype "passive"))
      (node (ref "C407") (pin "1") (pinfunction "1_1") (pintype "passive"))
      (node (ref "C408") (pin "1") (pinfunction "1_1") (pintype "passive"))
      (node (ref "C409") (pin "1") (pinfunction "1_1") (pintype "passive"))
      (node (ref "C410") (pin "1") (pinfunction "1_1") (pintype "passive"))
      (node (ref "C411") (pin "1") (pinfunction "1_1") (pintype "passive"))
      (node (ref "C415") (pin "1") (pinfunction "1_1") (pintype "passive"))
      (node (ref "C416") (pin "1") (pinfunction "1_1") (pintype "passive"))
      (node (ref "C417") (pin "1") (pinfunction "1_1") (pintype "passive"))
      (node (ref "C418") (pin "1") (pinfunction "1_1") (pintype "passive"))
      (node (ref "C521") (pin "1") (pinfunction "1_1") (pintype "passive"))
      (node (ref "C522") (pin "1") (pinfunction "1_1") (pintype "passive"))
      (node (ref "D1") (pin "B23") (pinfunction "VCCO_MIO0_500_B23") (pintype "power_in"))
      (node (ref "D1") (pin "C20") (pinfunction "VCCO_MIO1_501_C20") (pintype "power_in"))
      (node (ref "D1") (pin "E24") (pinfunction "VCCO_MIO0_500_E24") (pintype "power_in"))
      (node (ref "D1") (pin "F21") (pinfunction "VCCO_MIO0_500_F21") (pintype "power_in"))
      (node (ref "D1") (pin "G18") (pinfunction "VCCO_MIO1_501_G18") (pintype "power_in"))
      (node (ref "D1") (pin "J22") (pinfunction "VCCO_MIO1_501_J22") (pintype "power_in"))
      (node (ref "D1") (pin "K19") (pinfunction "VCCO_MIO1_501_K19") (pintype "power_in"))
      (node (ref "D1") (pin "M11") (pinfunction "VCCAUX_M11") (pintype "power_in"))
      (node (ref "D1") (pin "N10") (pinfunction "VCCAUX_N10") (pintype "power_in"))
      (node (ref "D1") (pin "N20") (pinfunction "VCCPAUX_N20") (pintype "power_in"))
      (node (ref "D1") (pin "P11") (pinfunction "VCCAUX_IO_G0_P11") (pintype "power_in"))
      (node (ref "D1") (pin "P19") (pinfunction "VCCPAUX_P19") (pintype "power_in"))
      (node (ref "D1") (pin "R10") (pinfunction "VCCAUX_R10") (pintype "power_in"))
      (node (ref "D1") (pin "R20") (pinfunction "VCCPAUX_R20") (pintype "power_in"))
      (node (ref "D1") (pin "T11") (pinfunction "VCCAUX_IO_G0_T11") (pintype "power_in"))
      (node (ref "D1") (pin "T7") (pinfunction "MGTVCCAUX_T7") (pintype "power_in"))
      (node (ref "D1") (pin "U10") (pinfunction "VCCAUX_U10") (pintype "power_in"))
      (node (ref "D1") (pin "U20") (pinfunction "VCCPAUX_U20") (pintype "power_in"))
      (node (ref "D1") (pin "V11") (pinfunction "VCCAUX_IO_G0_V11") (pintype "power_in"))
      (node (ref "D1") (pin "V7") (pinfunction "MGTVCCAUX_V7") (pintype "power_in"))
      (node (ref "D1") (pin "W10") (pinfunction "VCCAUX_W10") (pintype "power_in"))
      (node (ref "D1") (pin "Y11") (pinfunction "VCCAUX_Y11") (pintype "power_in"))
      (node (ref "L30") (pin "2") (pinfunction "2_2") (pintype "passive"))
      (node (ref "R250") (pin "2") (pintype "passive"))
    )
    (net (code "7") (name "VCC1V35") (class "Default")
      (node (ref "C397") (pin "1") (pinfunction "1_1") (pintype "passive"))
      (node (ref "C398") (pin "1") (pinfunction "1_1") (pintype "passive"))
      (node (ref "C399") (pin "1") (pinfunction "1_1") (pintype "passive"))
      (node (ref "C400") (pin "1") (pinfunction "1_1") (pintype "passive"))
      (node (ref "C401") (pin "1") (pinfunction "1_1") (pintype "passive"))
      (node (ref "C402") (pin "1") (pinfunction "1_1") (pintype "passive"))
      (node (ref "D1") (pin "A26") (pinfunction "VCCO_DDR_502_A26") (pintype "power_in"))
      (node (ref "D1") (pin "C30") (pinfunction "VCCO_DDR_502_C30") (pintype "power_in"))
      (node (ref "D1") (pin "D27") (pinfunction "VCCO_DDR_502_D27") (pintype "power_in"))
      (node (ref "D1") (pin "G28") (pinfunction "VCCO_DDR_502_G28") (pintype "power_in"))
      (node (ref "D1") (pin "H25") (pinfunction "VCCO_DDR_502_H25") (pintype "power_in"))
      (node (ref "D1") (pin "K29") (pinfunction "VCCO_DDR_502_K29") (pintype "power_in"))
      (node (ref "D1") (pin "L26") (pinfunction "VCCO_DDR_502_L26") (pintype "power_in"))
      (node (ref "D1") (pin "M23") (pinfunction "VCCO_DDR_502_M23") (pintype "power_in"))
    )
    (net (code "8") (name "VCC3V3") (class "Default")
      (node (ref "C414") (pin "1") (pinfunction "1_1") (pintype "passive"))
      (node (ref "D1") (pin "P15") (pinfunction "VCCADC_0_P15") (pintype "power_in"))
    )
  )
)
